# c64_mouse.net
KiCad netlist of a schematic drawn in EAGLE
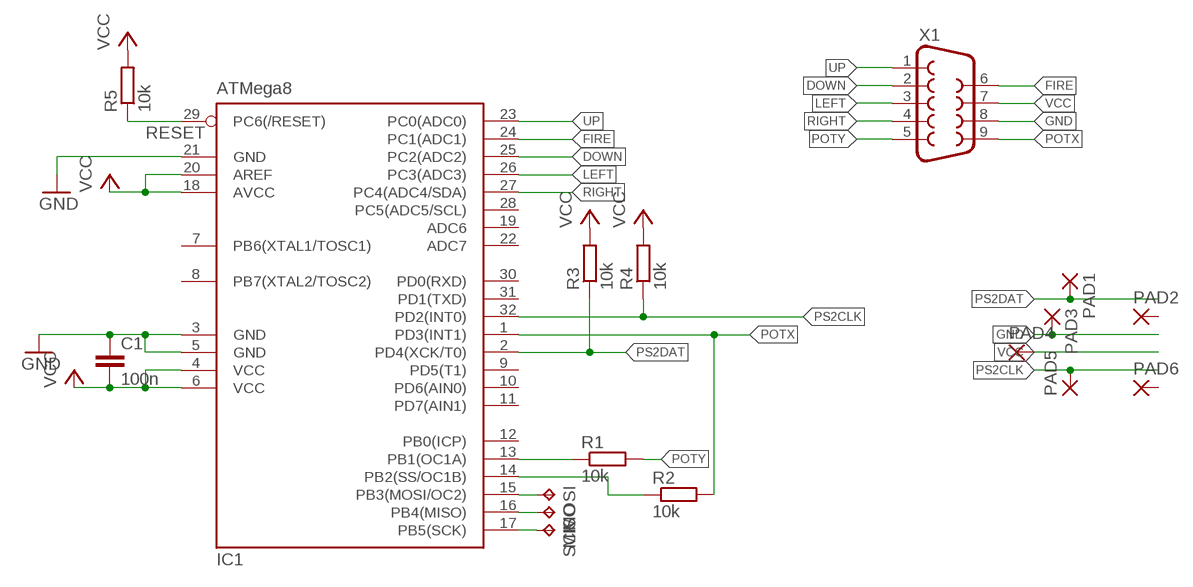
[diagram p0: schematic, sheet 1]

(export (version "E")
  (design (tool "Eeschema 10.0.6"))
  (components
    (comp (ref "C1")
      (value "100n")
      (footprint "eagle-import:C0805")
      (libsource (lib "eagle-import") (part "C-EUC0805"))
    )
    (comp (ref "IC1")
      (value "ATMega8")
      (footprint "eagle-import:TQFP32-08")
      (fields (field (name "MPN") "ATMEGA8-16AU"))
      (libsource (lib "eagle-import") (part "MEGA8-AI"))
    )
    (comp (ref "MISO")
      (value "TPB1,27")
      (footprint "eagle-import:B1,27")
      (libsource (lib "eagle-import") (part "TPB1,27"))
    )
    (comp (ref "MOSI")
      (value "TPB1,27")
      (footprint "eagle-import:B1,27")
      (libsource (lib "eagle-import") (part "TPB1,27"))
    )
    (comp (ref "PAD1")
      (value "SMD2")
      (footprint "eagle-import:SMD1,27-2,54")
      (libsource (lib "eagle-import") (part "SMD2"))
    )
    (comp (ref "PAD2")
      (value "SMD2")
      (footprint "eagle-import:SMD1,27-2,54")
      (libsource (lib "eagle-import") (part "SMD2"))
    )
    (comp (ref "PAD3")
      (value "SMD2")
      (footprint "eagle-import:SMD1,27-2,54")
      (libsource (lib "eagle-import") (part "SMD2"))
    )
    (comp (ref "PAD4")
      (value "SMD2")
      (footprint "eagle-import:SMD1,27-2,54")
      (libsource (lib "eagle-import") (part "SMD2"))
    )
    (comp (ref "PAD5")
      (value "SMD2")
      (footprint "eagle-import:SMD1,27-2,54")
      (libsource (lib "eagle-import") (part "SMD2"))
    )
    (comp (ref "PAD6")
      (value "SMD2")
      (footprint "eagle-import:SMD1,27-2,54")
      (libsource (lib "eagle-import") (part "SMD2"))
    )
    (comp (ref "R1")
      (value "10k")
      (footprint "eagle-import:R0805")
      (libsource (lib "eagle-import") (part "R-EU_R0805"))
    )
    (comp (ref "R2")
      (value "10k")
      (footprint "eagle-import:R0805")
      (libsource (lib "eagle-import") (part "R-EU_R0805"))
    )
    (comp (ref "R3")
      (value "10k")
      (footprint "eagle-import:R0805")
      (libsource (lib "eagle-import") (part "R-EU_R0805"))
    )
    (comp (ref "R4")
      (value "10k")
      (footprint "eagle-import:R0805")
      (libsource (lib "eagle-import") (part "R-EU_R0805"))
    )
    (comp (ref "R5")
      (value "10k")
      (footprint "eagle-import:R0805")
      (libsource (lib "eagle-import") (part "R-EU_R0805"))
    )
    (comp (ref "SCK")
      (value "TPB1,27")
      (footprint "eagle-import:B1,27")
      (libsource (lib "eagle-import") (part "TPB1,27"))
    )
    (comp (ref "X1")
      (value "F09D")
      (footprint "eagle-import:F09D")
      (libsource (lib "eagle-import") (part "F09D"))
    )
  )
  (nets
    (net (code "1") (name "/RESET") (class "Default")
      (node (ref "IC1") (pin "29") (pinfunction "PC6(/RESET)_29") (pintype "bidirectional"))
      (node (ref "R5") (pin "1") (pinfunction "1_1") (pintype "passive"))
    )
    (net (code "2") (name "DOWN") (class "Default")
      (node (ref "IC1") (pin "25") (pinfunction "PC2(ADC2)_25") (pintype "bidirectional"))
      (node (ref "X1") (pin "2") (pinfunction "2_2") (pintype "passive"))
    )
    (net (code "3") (name "FIRE") (class "Default")
      (node (ref "IC1") (pin "24") (pinfunction "PC1(ADC1)_24") (pintype "bidirectional"))
      (node (ref "X1") (pin "6") (pinfunction "6_6") (pintype "passive"))
    )
    (net (code "4") (name "GND") (class "Default")
      (node (ref "C1") (pin "1") (pinfunction "1_1") (pintype "passive"))
      (node (ref "IC1") (pin "21") (pinfunction "GND_21") (pintype "power_in"))
      (node (ref "IC1") (pin "3") (pinfunction "GND_3") (pintype "power_in"))
      (node (ref "IC1") (pin "5") (pinfunction "GND_5") (pintype "power_in"))
      (node (ref "PAD3") (pin "1") (pinfunction "P_1") (pintype "passive"))
      (node (ref "X1") (pin "8") (pinfunction "8_8") (pintype "passive"))
    )
    (net (code "5") (name "LEFT") (class "Default")
      (node (ref "IC1") (pin "26") (pinfunction "PC3(ADC3)_26") (pintype "bidirectional"))
      (node (ref "X1") (pin "3") (pinfunction "3_3") (pintype "passive"))
    )
    (net (code "6") (name "Net-(IC1-PB1(OC1A))") (class "Default")
      (node (ref "IC1") (pin "13") (pinfunction "PB1(OC1A)_13") (pintype "bidirectional"))
      (node (ref "R1") (pin "1") (pinfunction "1_1") (pintype "passive"))
    )
    (net (code "7") (name "Net-(IC1-PB2(SS{slash}OC1B))") (class "Default")
      (node (ref "IC1") (pin "14") (pinfunction "PB2(SS/OC1B)_14") (pintype "bidirectional"))
      (node (ref "R2") (pin "1") (pinfunction "1_1") (pintype "passive"))
    )
    (net (code "8") (name "Net-(IC1-PB3(MOSI{slash}OC2))") (class "Default")
      (node (ref "IC1") (pin "15") (pinfunction "PB3(MOSI/OC2)_15") (pintype "bidirectional"))
      (node (ref "MOSI") (pin "TP") (pinfunction "TP_TP") (pintype "input"))
    )
    (net (code "9") (name "Net-(IC1-PB4(MISO))") (class "Default")
      (node (ref "IC1") (pin "16") (pinfunction "PB4(MISO)_16") (pintype "bidirectional"))
      (node (ref "MISO") (pin "TP") (pinfunction "TP_TP") (pintype "input"))
    )
    (net (code "10") (name "Net-(IC1-PB5(SCK))") (class "Default")
      (node (ref "IC1") (pin "17") (pinfunction "PB5(SCK)_17") (pintype "bidirectional"))
      (node (ref "SCK") (pin "TP") (pinfunction "TP_TP") (pintype "input"))
    )
    (net (code "11") (name "POTX") (class "Default")
      (node (ref "IC1") (pin "1") (pinfunction "PD3(INT1)_1") (pintype "bidirectional"))
      (node (ref "R2") (pin "2") (pinfunction "2_2") (pintype "passive"))
      (node (ref "X1") (pin "9") (pinfunction "9_9") (pintype "passive"))
    )
    (net (code "12") (name "POTY") (class "Default")
      (node (ref "R1") (pin "2") (pinfunction "2_2") (pintype "passive"))
      (node (ref "X1") (pin "5") (pinfunction "5_5") (pintype "passive"))
    )
    (net (code "13") (name "PS2CLK") (class "Default")
      (node (ref "IC1") (pin "32") (pinfunction "PD2(INT0)_32") (pintype "bidirectional"))
      (node (ref "PAD5") (pin "1") (pinfunction "P_1") (pintype "passive"))
      (node (ref "R4") (pin "1") (pinfunction "1_1") (pintype "passive"))
    )
    (net (code "14") (name "PS2DAT") (class "Default")
      (node (ref "IC1") (pin "2") (pinfunction "PD4(XCK/T0)_2") (pintype "bidirectional"))
      (node (ref "PAD1") (pin "1") (pinfunction "P_1") (pintype "passive"))
      (node (ref "R3") (pin "1") (pinfunction "1_1") (pintype "passive"))
    )
    (net (code "15") (name "RIGHT") (class "Default")
      (node (ref "IC1") (pin "27") (pinfunction "PC4(ADC4/SDA)_27") (pintype "bidirectional"))
      (node (ref "X1") (pin "4") (pinfunction "4_4") (pintype "passive"))
    )
    (net (code "16") (name "UP") (class "Default")
      (node (ref "IC1") (pin "23") (pinfunction "PC0(ADC0)_23") (pintype "bidirectional"))
      (node (ref "X1") (pin "1") (pinfunction "1_1") (pintype "passive"))
    )
    (net (code "17") (name "VCC") (class "Default")
      (node (ref "C1") (pin "2") (pinfunction "2_2") (pintype "passive"))
      (node (ref "IC1") (pin "18") (pinfunction "AVCC_18") (pintype "power_in"))
      (node (ref "IC1") (pin "20") (pinfunction "AREF_20") (pintype "passive"))
      (node (ref "IC1") (pin "4") (pinfunction "VCC_4") (pintype "power_in"))
      (node (ref "IC1") (pin "6") (pinfunction "VCC_6") (pintype "power_in"))
      (node (ref "PAD4") (pin "1") (pinfunction "P_1") (pintype "passive"))
      (node (ref "R3") (pin "2") (pinfunction "2_2") (pintype "passive"))
      (node (ref "R4") (pin "2") (pinfunction "2_2") (pintype "passive"))
      (node (ref "R5") (pin "2") (pinfunction "2_2") (pintype "passive"))
      (node (ref "X1") (pin "7") (pinfunction "7_7") (pintype "passive"))
    )
    (net (code "18") (name "unconnected-(IC1-ADC6-Pad19)") (class "Default")
      (node (ref "IC1") (pin "19") (pinfunction "ADC6_19") (pintype "bidirectional"))
    )
    (net (code "19") (name "unconnected-(IC1-ADC7-Pad22)") (class "Default")
      (node (ref "IC1") (pin "22") (pinfunction "ADC7_22") (pintype "bidirectional"))
    )
    (net (code "20") (name "unconnected-(IC1-PB0(ICP)-Pad12)") (class "Default")
      (node (ref "IC1") (pin "12") (pinfunction "PB0(ICP)_12") (pintype "bidirectional"))
    )
    (net (code "21") (name "unconnected-(IC1-PB6(XTAL1{slash}TOSC1)-Pad7)") (class "Default")
      (node (ref "IC1") (pin "7") (pinfunction "PB6(XTAL1/TOSC1)_7") (pintype "bidirectional"))
    )
    (net (code "22") (name "unconnected-(IC1-PB7(XTAL2{slash}TOSC2)-Pad8)") (class "Default")
      (node (ref "IC1") (pin "8") (pinfunction "PB7(XTAL2/TOSC2)_8") (pintype "bidirectional"))
    )
    (net (code "23") (name "unconnected-(IC1-PC5(ADC5{slash}SCL)-Pad28)") (class "Default")
      (node (ref "IC1") (pin "28") (pinfunction "PC5(ADC5/SCL)_28") (pintype "bidirectional"))
    )
    (net (code "24") (name "unconnected-(IC1-PD0(RXD)-Pad30)") (class "Default")
      (node (ref "IC1") (pin "30") (pinfunction "PD0(RXD)_30") (pintype "bidirectional"))
    )
    (net (code "25") (name "unconnected-(IC1-PD1(TXD)-Pad31)") (class "Default")
      (node (ref "IC1") (pin "31") (pinfunction "PD1(TXD)_31") (pintype "bidirectional"))
    )
    (net (code "26") (name "unconnected-(IC1-PD5(T1)-Pad9)") (class "Default")
      (node (ref "IC1") (pin "9") (pinfunction "PD5(T1)_9") (pintype "bidirectional"))
    )
    (net (code "27") (name "unconnected-(IC1-PD6(AIN0)-Pad10)") (class "Default")
      (node (ref "IC1") (pin "10") (pinfunction "PD6(AIN0)_10") (pintype "bidirectional"))
    )
    (net (code "28") (name "unconnected-(IC1-PD7(AIN1)-Pad11)") (class "Default")
      (node (ref "IC1") (pin "11") (pinfunction "PD7(AIN1)_11") (pintype "bidirectional"))
    )
    (net (code "29") (name "unconnected-(PAD2-P-Pad1)") (class "Default")
      (node (ref "PAD2") (pin "1") (pinfunction "P_1") (pintype "passive"))
    )
    (net (code "30") (name "unconnected-(PAD6-P-Pad1)") (class "Default")
      (node (ref "PAD6") (pin "1") (pinfunction "P_1") (pintype "passive"))
    )
  )
)
